# 325V-DC-Motor-on-Phase-Control_Principle.net
KiCad netlist of a schematic drawn in EAGLE
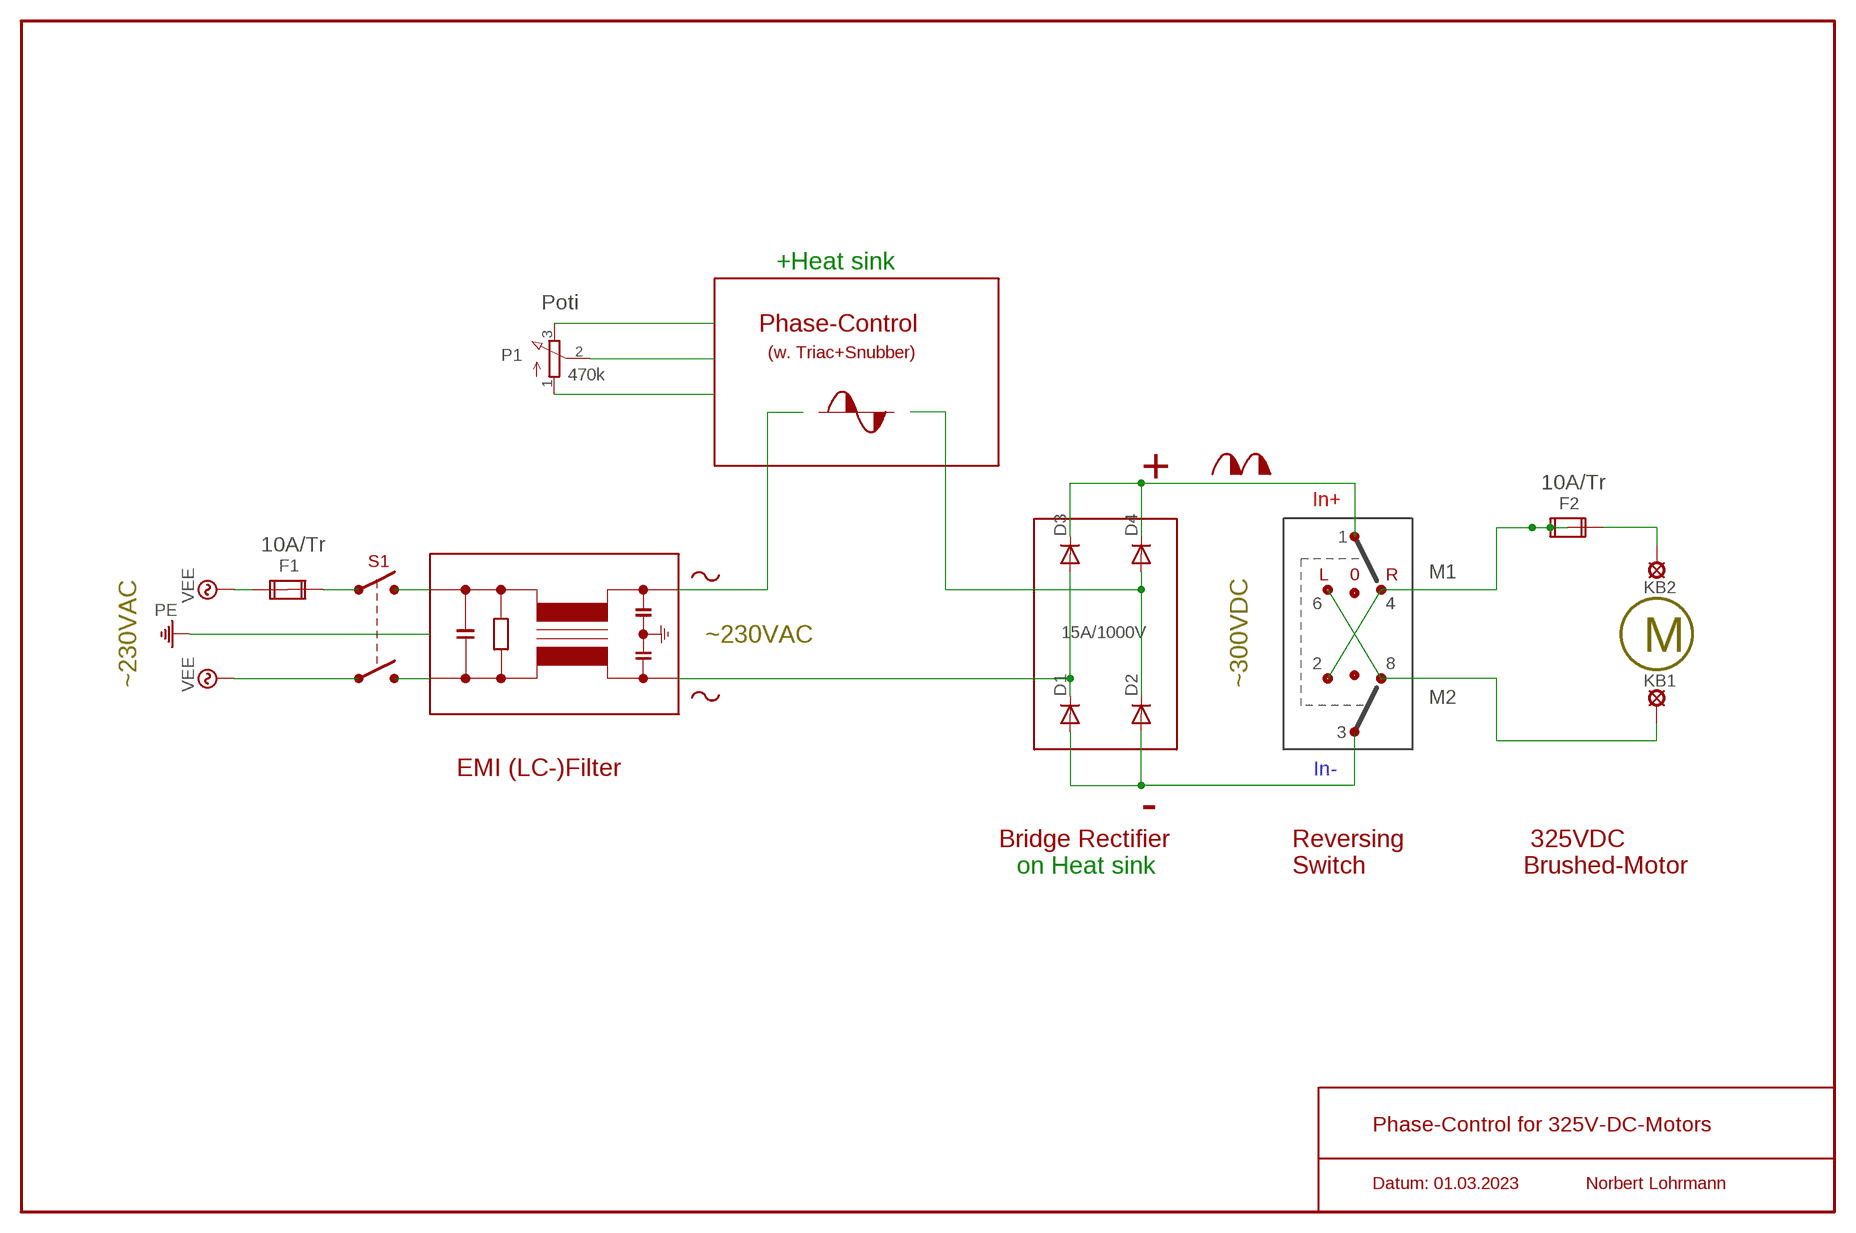
[diagram p0: schematic, sheet 1]

(export (version "E")
  (design (tool "Eeschema 10.0.6"))
  (components
    (comp (ref "D1")
      (value "DIODE-D-2.5")
      (footprint "eagle-import:D-2.5")
      (libsource (lib "eagle-import") (part "DIODE-D-2.5"))
    )
    (comp (ref "D2")
      (value "DIODE-D-2.5")
      (footprint "eagle-import:D-2.5")
      (libsource (lib "eagle-import") (part "DIODE-D-2.5"))
    )
    (comp (ref "D3")
      (value "DIODE-D-2.5")
      (footprint "eagle-import:D-2.5")
      (libsource (lib "eagle-import") (part "DIODE-D-2.5"))
    )
    (comp (ref "D4")
      (value "DIODE-D-2.5")
      (footprint "eagle-import:D-2.5")
      (libsource (lib "eagle-import") (part "DIODE-D-2.5"))
    )
    (comp (ref "F1")
      (value "10A/Tr")
      (footprint "eagle-import:FUSE1")
      (libsource (lib "eagle-import") (part "FUSE2P"))
    )
    (comp (ref "F2")
      (value "10A/Tr")
      (footprint "eagle-import:FUSE1")
      (libsource (lib "eagle-import") (part "FUSE2P"))
    )
    (comp (ref "KB1")
      (value "LSP10")
      (footprint "eagle-import:LSP10")
      (libsource (lib "eagle-import") (part "LSP10"))
    )
    (comp (ref "KB2")
      (value "LSP10")
      (footprint "eagle-import:LSP10")
      (libsource (lib "eagle-import") (part "LSP10"))
    )
    (comp (ref "P1")
      (value "Poti")
      (footprint "eagle-import:3RP_1610N")
      (libsource (lib "eagle-import") (part "3RP/1610N"))
    )
  )
  (nets
    (net (code "1") (name "Net-(D1-PadA)") (class "Default")
      (node (ref "D1") (pin "A") (pinfunction "A_A") (pintype "passive"))
      (node (ref "D2") (pin "A") (pinfunction "A_A") (pintype "passive"))
    )
    (net (code "2") (name "Net-(D1-PadC)") (class "Default")
      (node (ref "D1") (pin "C") (pinfunction "C_C") (pintype "passive"))
      (node (ref "D3") (pin "A") (pinfunction "A_A") (pintype "passive"))
    )
    (net (code "3") (name "Net-(D2-PadC)") (class "Default")
      (node (ref "D2") (pin "C") (pinfunction "C_C") (pintype "passive"))
      (node (ref "D4") (pin "A") (pinfunction "A_A") (pintype "passive"))
    )
    (net (code "4") (name "Net-(D3-PadC)") (class "Default")
      (node (ref "D3") (pin "C") (pinfunction "C_C") (pintype "passive"))
      (node (ref "D4") (pin "C") (pinfunction "C_C") (pintype "passive"))
    )
    (net (code "5") (name "Net-(F2-Pad1A)") (class "Default")
      (node (ref "F2") (pin "1A") (pinfunction "1A_1A") (pintype "passive"))
      (node (ref "F2") (pin "1B") (pinfunction "1B_1B") (pintype "passive"))
    )
    (net (code "6") (name "Net-(F2-Pad2A)") (class "Default")
      (node (ref "F2") (pin "2A") (pinfunction "2A_2A") (pintype "passive"))
      (node (ref "KB2") (pin "MP") (pinfunction "MP_MP") (pintype "passive"))
    )
    (net (code "8") (name "VEE") (class "Default")
      (node (ref "F1") (pin "1A") (pinfunction "1A_1A") (pintype "passive"))
    )
    (net (code "9") (name "unconnected-(F1-Pad1B)") (class "Default")
      (node (ref "F1") (pin "1B") (pinfunction "1B_1B") (pintype "passive"))
    )
    (net (code "10") (name "unconnected-(F1-Pad2A)") (class "Default")
      (node (ref "F1") (pin "2A") (pinfunction "2A_2A") (pintype "passive"))
    )
    (net (code "11") (name "unconnected-(F1-Pad2B)") (class "Default")
      (node (ref "F1") (pin "2B") (pinfunction "2B_2B") (pintype "passive"))
    )
    (net (code "12") (name "unconnected-(F2-Pad2B)") (class "Default")
      (node (ref "F2") (pin "2B") (pinfunction "2B_2B") (pintype "passive"))
    )
    (net (code "13") (name "unconnected-(KB1-PadMP)") (class "Default")
      (node (ref "KB1") (pin "MP") (pinfunction "MP_MP") (pintype "passive"))
    )
    (net (code "14") (name "unconnected-(P1-A-Pad1)") (class "Default")
      (node (ref "P1") (pin "1") (pinfunction "A_1") (pintype "passive"))
    )
    (net (code "15") (name "unconnected-(P1-E-Pad3)") (class "Default")
      (node (ref "P1") (pin "3") (pinfunction "E_3") (pintype "passive"))
    )
    (net (code "16") (name "unconnected-(P1-S-Pad2)") (class "Default")
      (node (ref "P1") (pin "2") (pinfunction "S_2") (pintype "passive"))
    )
  )
)
